# driver_board_v6_6tubes.net
KiCad netlist of a schematic drawn in EAGLE
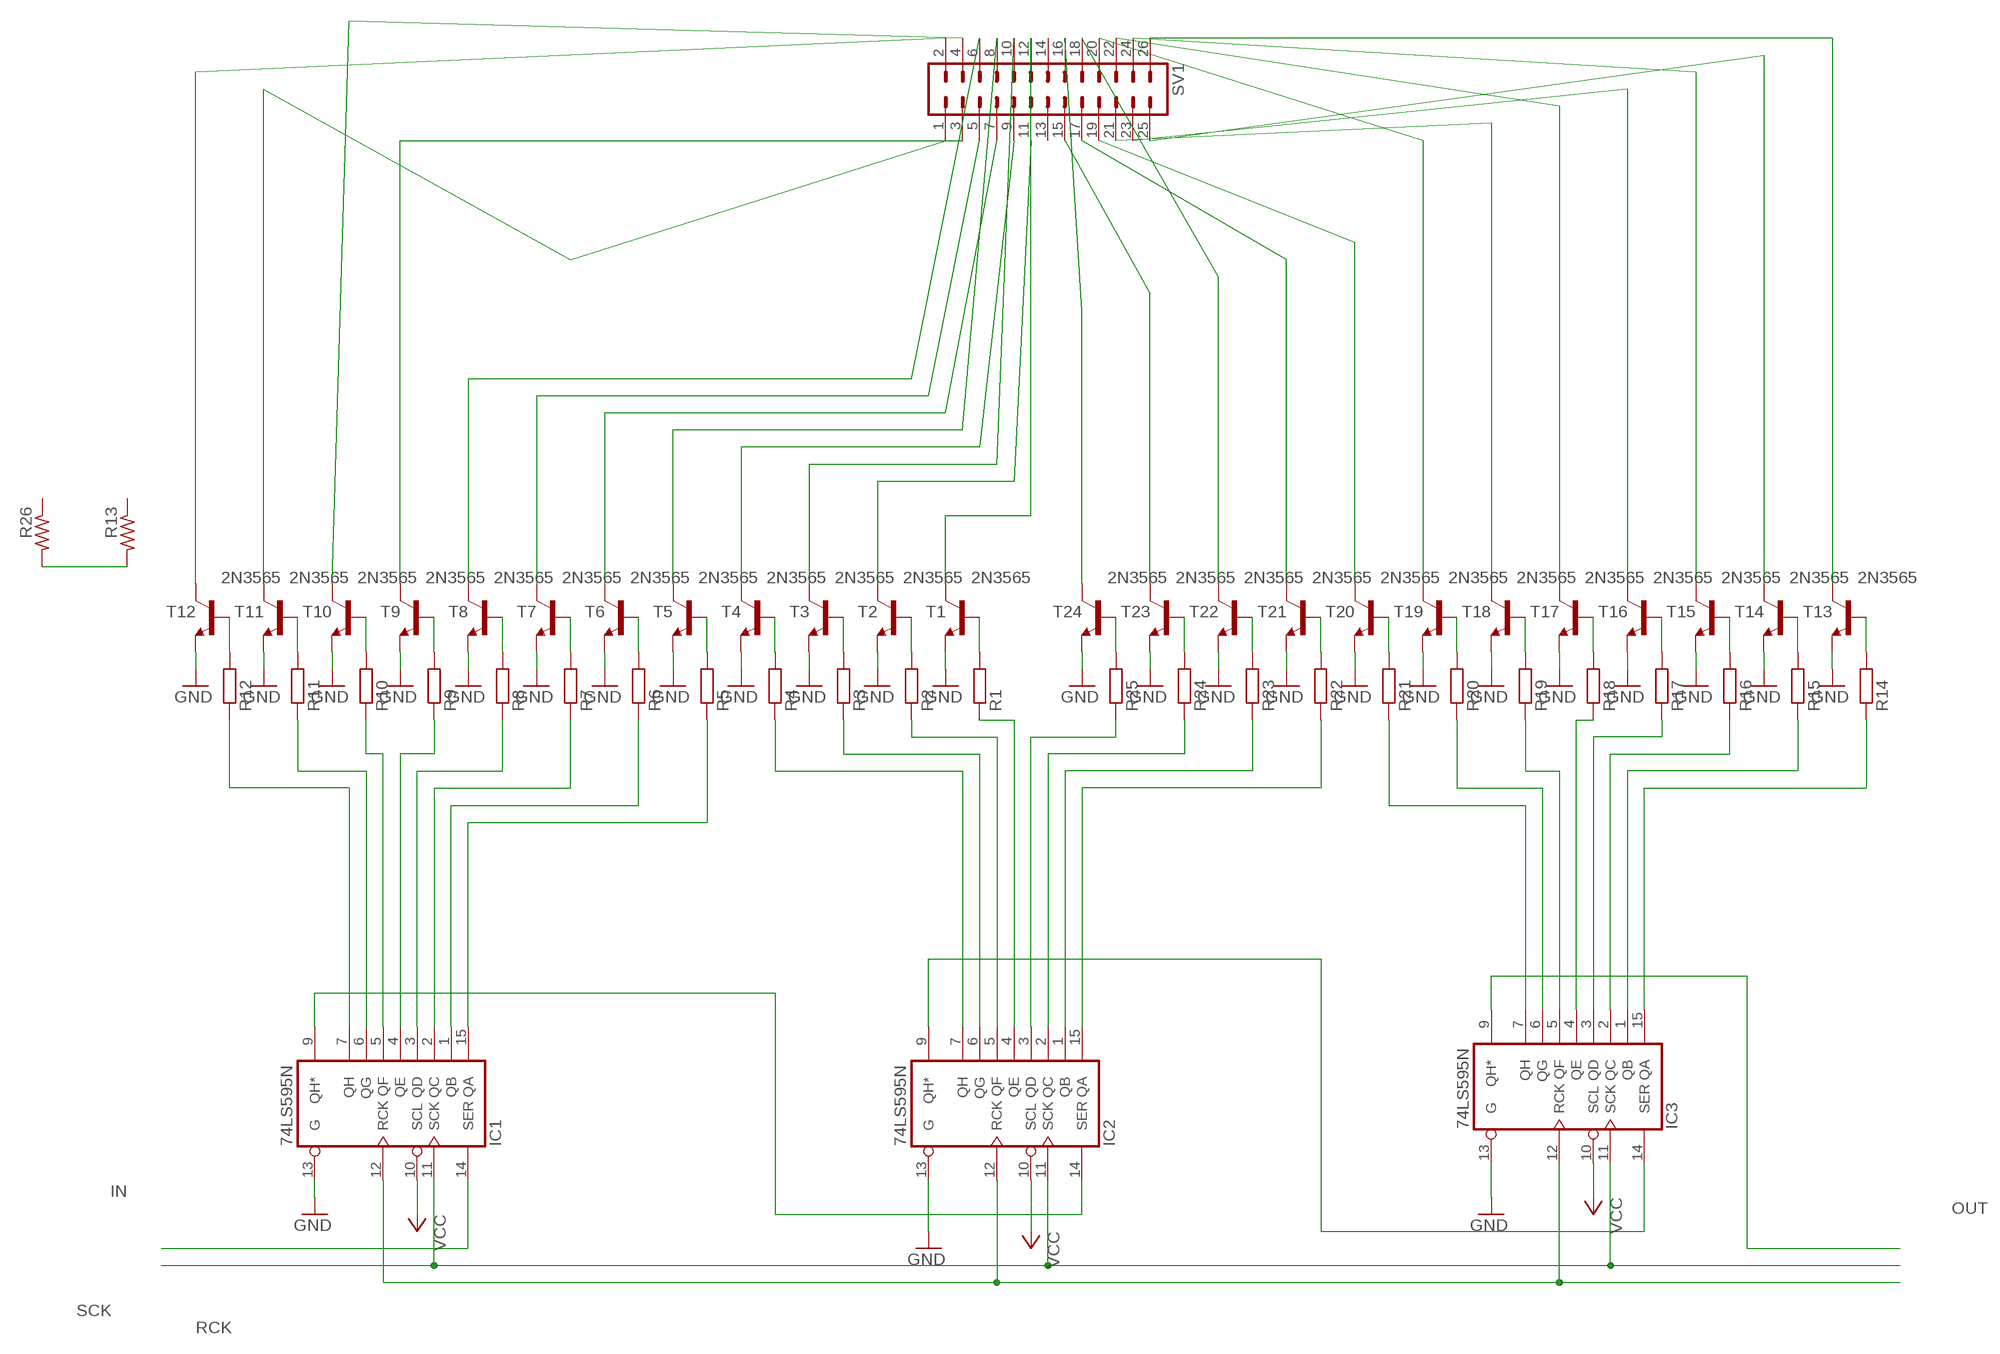
[diagram p0: schematic, sheet 1, part 1 of 2]
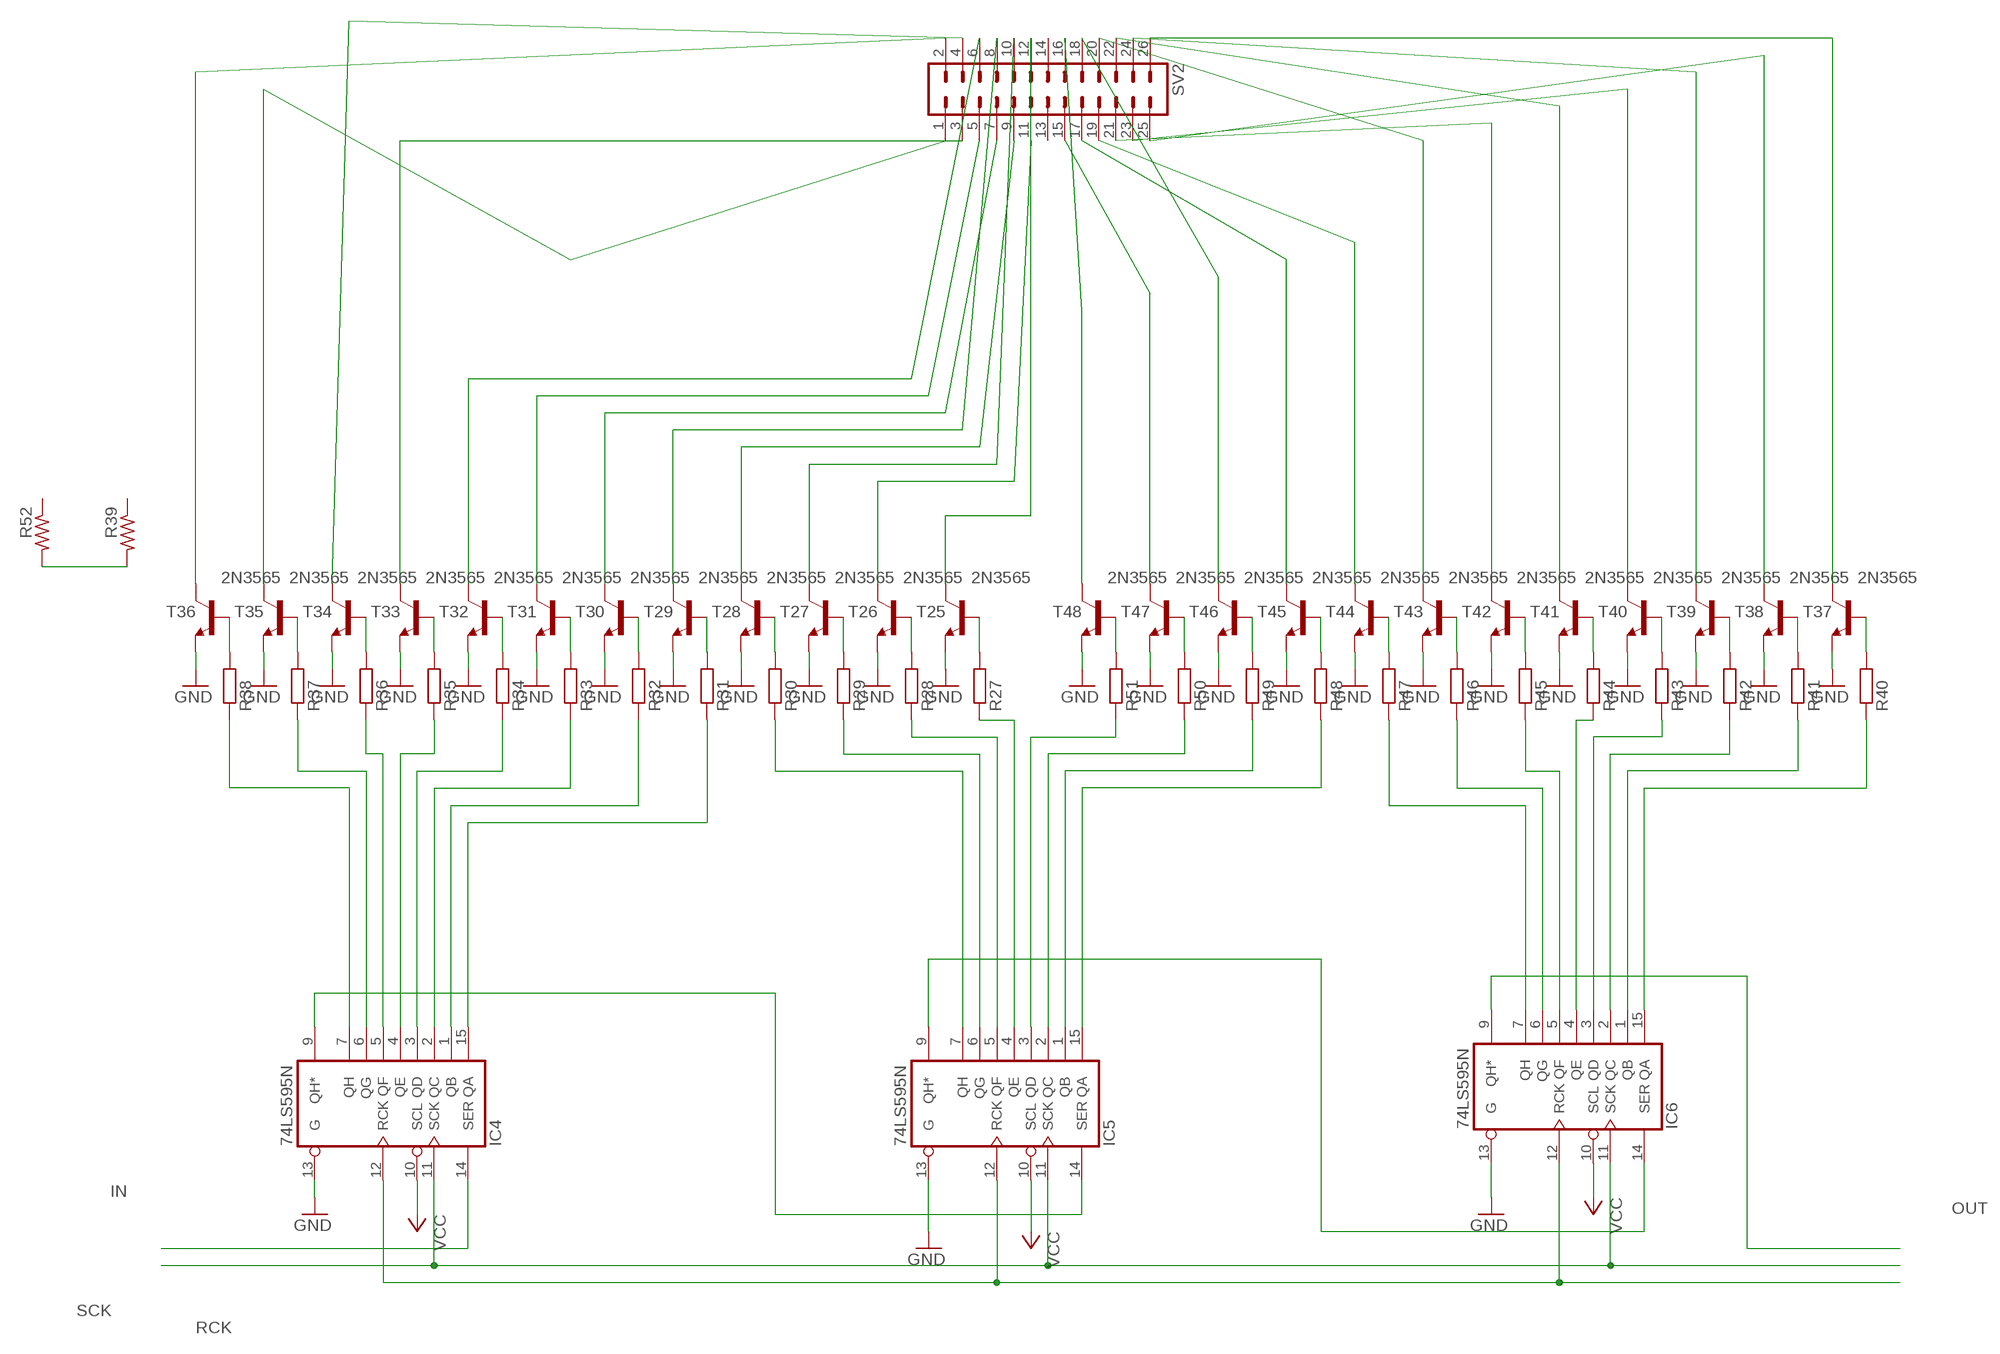
[diagram p1: schematic, sheet 1, part 2 of 2]

(export (version "E")
  (design (tool "Eeschema 10.0.6"))
  (components
    (comp (ref "IC1")
      (value "74LS595N")
      (footprint "eagle-import:DIL16")
      (libsource (lib "eagle-import") (part "74595NLS"))
    )
    (comp (ref "IC2")
      (value "74LS595N")
      (footprint "eagle-import:DIL16")
      (libsource (lib "eagle-import") (part "74595NLS"))
    )
    (comp (ref "IC3")
      (value "74LS595N")
      (footprint "eagle-import:DIL16")
      (libsource (lib "eagle-import") (part "74595NLS"))
    )
    (comp (ref "IC4")
      (value "74LS595N")
      (footprint "eagle-import:DIL16")
      (libsource (lib "eagle-import") (part "74595NLS"))
    )
    (comp (ref "IC5")
      (value "74LS595N")
      (footprint "eagle-import:DIL16")
      (libsource (lib "eagle-import") (part "74595NLS"))
    )
    (comp (ref "IC6")
      (value "74LS595N")
      (footprint "eagle-import:DIL16")
      (libsource (lib "eagle-import") (part "74595NLS"))
    )
    (comp (ref "R1")
      (value "R-EU_0207/2V")
      (footprint "eagle-import:0207_2V")
      (libsource (lib "eagle-import") (part "R-EU_0207/2V"))
    )
    (comp (ref "R2")
      (value "R-EU_0207/2V")
      (footprint "eagle-import:0207_2V")
      (libsource (lib "eagle-import") (part "R-EU_0207/2V"))
    )
    (comp (ref "R3")
      (value "R-EU_0207/2V")
      (footprint "eagle-import:0207_2V")
      (libsource (lib "eagle-import") (part "R-EU_0207/2V"))
    )
    (comp (ref "R4")
      (value "R-EU_0207/2V")
      (footprint "eagle-import:0207_2V")
      (libsource (lib "eagle-import") (part "R-EU_0207/2V"))
    )
    (comp (ref "R5")
      (value "R-EU_0207/2V")
      (footprint "eagle-import:0207_2V")
      (libsource (lib "eagle-import") (part "R-EU_0207/2V"))
    )
    (comp (ref "R6")
      (value "R-EU_0207/2V")
      (footprint "eagle-import:0207_2V")
      (libsource (lib "eagle-import") (part "R-EU_0207/2V"))
    )
    (comp (ref "R7")
      (value "R-EU_0207/2V")
      (footprint "eagle-import:0207_2V")
      (libsource (lib "eagle-import") (part "R-EU_0207/2V"))
    )
    (comp (ref "R8")
      (value "R-EU_0207/2V")
      (footprint "eagle-import:0207_2V")
      (libsource (lib "eagle-import") (part "R-EU_0207/2V"))
    )
    (comp (ref "R9")
      (value "R-EU_0207/2V")
      (footprint "eagle-import:0207_2V")
      (libsource (lib "eagle-import") (part "R-EU_0207/2V"))
    )
    (comp (ref "R10")
      (value "R-EU_0207/2V")
      (footprint "eagle-import:0207_2V")
      (libsource (lib "eagle-import") (part "R-EU_0207/2V"))
    )
    (comp (ref "R11")
      (value "R-EU_0207/2V")
      (footprint "eagle-import:0207_2V")
      (libsource (lib "eagle-import") (part "R-EU_0207/2V"))
    )
    (comp (ref "R12")
      (value "R-EU_0207/2V")
      (footprint "eagle-import:0207_2V")
      (libsource (lib "eagle-import") (part "R-EU_0207/2V"))
    )
    (comp (ref "R13")
      (value "R-US_0204/7")
      (footprint "eagle-import:0204_7")
      (libsource (lib "eagle-import") (part "R-US_0204/7"))
    )
    (comp (ref "R14")
      (value "R-EU_0207/2V")
      (footprint "eagle-import:0207_2V")
      (libsource (lib "eagle-import") (part "R-EU_0207/2V"))
    )
    (comp (ref "R15")
      (value "R-EU_0207/2V")
      (footprint "eagle-import:0207_2V")
      (libsource (lib "eagle-import") (part "R-EU_0207/2V"))
    )
    (comp (ref "R16")
      (value "R-EU_0207/2V")
      (footprint "eagle-import:0207_2V")
      (libsource (lib "eagle-import") (part "R-EU_0207/2V"))
    )
    (comp (ref "R17")
      (value "R-EU_0207/2V")
      (footprint "eagle-import:0207_2V")
      (libsource (lib "eagle-import") (part "R-EU_0207/2V"))
    )
    (comp (ref "R18")
      (value "R-EU_0207/2V")
      (footprint "eagle-import:0207_2V")
      (libsource (lib "eagle-import") (part "R-EU_0207/2V"))
    )
    (comp (ref "R19")
      (value "R-EU_0207/2V")
      (footprint "eagle-import:0207_2V")
      (libsource (lib "eagle-import") (part "R-EU_0207/2V"))
    )
    (comp (ref "R20")
      (value "R-EU_0207/2V")
      (footprint "eagle-import:0207_2V")
      (libsource (lib "eagle-import") (part "R-EU_0207/2V"))
    )
    (comp (ref "R21")
      (value "R-EU_0207/2V")
      (footprint "eagle-import:0207_2V")
      (libsource (lib "eagle-import") (part "R-EU_0207/2V"))
    )
    (comp (ref "R22")
      (value "R-EU_0207/2V")
      (footprint "eagle-import:0207_2V")
      (libsource (lib "eagle-import") (part "R-EU_0207/2V"))
    )
    (comp (ref "R23")
      (value "R-EU_0207/2V")
      (footprint "eagle-import:0207_2V")
      (libsource (lib "eagle-import") (part "R-EU_0207/2V"))
    )
    (comp (ref "R24")
      (value "R-EU_0207/2V")
      (footprint "eagle-import:0207_2V")
      (libsource (lib "eagle-import") (part "R-EU_0207/2V"))
    )
    (comp (ref "R25")
      (value "R-EU_0207/2V")
      (footprint "eagle-import:0207_2V")
      (libsource (lib "eagle-import") (part "R-EU_0207/2V"))
    )
    (comp (ref "R26")
      (value "R-US_0204/7")
      (footprint "eagle-import:0204_7")
      (libsource (lib "eagle-import") (part "R-US_0204/7"))
    )
    (comp (ref "R27")
      (value "R-EU_0207/2V")
      (footprint "eagle-import:0207_2V")
      (libsource (lib "eagle-import") (part "R-EU_0207/2V"))
    )
    (comp (ref "R28")
      (value "R-EU_0207/2V")
      (footprint "eagle-import:0207_2V")
      (libsource (lib "eagle-import") (part "R-EU_0207/2V"))
    )
    (comp (ref "R29")
      (value "R-EU_0207/2V")
      (footprint "eagle-import:0207_2V")
      (libsource (lib "eagle-import") (part "R-EU_0207/2V"))
    )
    (comp (ref "R30")
      (value "R-EU_0207/2V")
      (footprint "eagle-import:0207_2V")
      (libsource (lib "eagle-import") (part "R-EU_0207/2V"))
    )
    (comp (ref "R31")
      (value "R-EU_0207/2V")
      (footprint "eagle-import:0207_2V")
      (libsource (lib "eagle-import") (part "R-EU_0207/2V"))
    )
    (comp (ref "R32")
      (value "R-EU_0207/2V")
      (footprint "eagle-import:0207_2V")
      (libsource (lib "eagle-import") (part "R-EU_0207/2V"))
    )
    (comp (ref "R33")
      (value "R-EU_0207/2V")
      (footprint "eagle-import:0207_2V")
      (libsource (lib "eagle-import") (part "R-EU_0207/2V"))
    )
    (comp (ref "R34")
      (value "R-EU_0207/2V")
      (footprint "eagle-import:0207_2V")
      (libsource (lib "eagle-import") (part "R-EU_0207/2V"))
    )
    (comp (ref "R35")
      (value "R-EU_0207/2V")
      (footprint "eagle-import:0207_2V")
      (libsource (lib "eagle-import") (part "R-EU_0207/2V"))
    )
    (comp (ref "R36")
      (value "R-EU_0207/2V")
      (footprint "eagle-import:0207_2V")
      (libsource (lib "eagle-import") (part "R-EU_0207/2V"))
    )
    (comp (ref "R37")
      (value "R-EU_0207/2V")
      (footprint "eagle-import:0207_2V")
      (libsource (lib "eagle-import") (part "R-EU_0207/2V"))
    )
    (comp (ref "R38")
      (value "R-EU_0207/2V")
      (footprint "eagle-import:0207_2V")
      (libsource (lib "eagle-import") (part "R-EU_0207/2V"))
    )
    (comp (ref "R39")
      (value "R-US_0204/7")
      (footprint "eagle-import:0204_7")
      (libsource (lib "eagle-import") (part "R-US_0204/7"))
    )
    (comp (ref "R40")
      (value "R-EU_0207/2V")
      (footprint "eagle-import:0207_2V")
      (libsource (lib "eagle-import") (part "R-EU_0207/2V"))
    )
    (comp (ref "R41")
      (value "R-EU_0207/2V")
      (footprint "eagle-import:0207_2V")
      (libsource (lib "eagle-import") (part "R-EU_0207/2V"))
    )
    (comp (ref "R42")
      (value "R-EU_0207/2V")
      (footprint "eagle-import:0207_2V")
      (libsource (lib "eagle-import") (part "R-EU_0207/2V"))
    )
    (comp (ref "R43")
      (value "R-EU_0207/2V")
      (footprint "eagle-import:0207_2V")
      (libsource (lib "eagle-import") (part "R-EU_0207/2V"))
    )
    (comp (ref "R44")
      (value "R-EU_0207/2V")
      (footprint "eagle-import:0207_2V")
      (libsource (lib "eagle-import") (part "R-EU_0207/2V"))
    )
    (comp (ref "R45")
      (value "R-EU_0207/2V")
      (footprint "eagle-import:0207_2V")
      (libsource (lib "eagle-import") (part "R-EU_0207/2V"))
    )
    (comp (ref "R46")
      (value "R-EU_0207/2V")
      (footprint "eagle-import:0207_2V")
      (libsource (lib "eagle-import") (part "R-EU_0207/2V"))
    )
    (comp (ref "R47")
      (value "R-EU_0207/2V")
      (footprint "eagle-import:0207_2V")
      (libsource (lib "eagle-import") (part "R-EU_0207/2V"))
    )
    (comp (ref "R48")
      (value "R-EU_0207/2V")
      (footprint "eagle-import:0207_2V")
      (libsource (lib "eagle-import") (part "R-EU_0207/2V"))
    )
    (comp (ref "R49")
      (value "R-EU_0207/2V")
      (footprint "eagle-import:0207_2V")
      (libsource (lib "eagle-import") (part "R-EU_0207/2V"))
    )
    (comp (ref "R50")
      (value "R-EU_0207/2V")
      (footprint "eagle-import:0207_2V")
      (libsource (lib "eagle-import") (part "R-EU_0207/2V"))
    )
    (comp (ref "R51")
      (value "R-EU_0207/2V")
      (footprint "eagle-import:0207_2V")
      (libsource (lib "eagle-import") (part "R-EU_0207/2V"))
    )
    (comp (ref "R52")
      (value "R-US_0204/7")
      (footprint "eagle-import:0204_7")
      (libsource (lib "eagle-import") (part "R-US_0204/7"))
    )
    (comp (ref "SV1")
      (value "MA13-2")
      (footprint "eagle-import:MA13-2")
      (libsource (lib "eagle-import") (part "MA13-2"))
    )
    (comp (ref "SV2")
      (value "MA13-2")
      (footprint "eagle-import:MA13-2")
      (libsource (lib "eagle-import") (part "MA13-2"))
    )
    (comp (ref "T1")
      (value "2N3565")
      (footprint "eagle-import:TO92")
      (libsource (lib "eagle-import") (part "2N3565"))
    )
    (comp (ref "T2")
      (value "2N3565")
      (footprint "eagle-import:TO92")
      (libsource (lib "eagle-import") (part "2N3565"))
    )
    (comp (ref "T3")
      (value "2N3565")
      (footprint "eagle-import:TO92")
      (libsource (lib "eagle-import") (part "2N3565"))
    )
    (comp (ref "T4")
      (value "2N3565")
      (footprint "eagle-import:TO92")
      (libsource (lib "eagle-import") (part "2N3565"))
    )
    (comp (ref "T5")
      (value "2N3565")
      (footprint "eagle-import:TO92")
      (libsource (lib "eagle-import") (part "2N3565"))
    )
    (comp (ref "T6")
      (value "2N3565")
      (footprint "eagle-import:TO92")
      (libsource (lib "eagle-import") (part "2N3565"))
    )
    (comp (ref "T7")
      (value "2N3565")
      (footprint "eagle-import:TO92")
      (libsource (lib "eagle-import") (part "2N3565"))
    )
    (comp (ref "T8")
      (value "2N3565")
      (footprint "eagle-import:TO92")
      (libsource (lib "eagle-import") (part "2N3565"))
    )
    (comp (ref "T9")
      (value "2N3565")
      (footprint "eagle-import:TO92")
      (libsource (lib "eagle-import") (part "2N3565"))
    )
    (comp (ref "T10")
      (value "2N3565")
      (footprint "eagle-import:TO92")
      (libsource (lib "eagle-import") (part "2N3565"))
    )
    (comp (ref "T11")
      (value "2N3565")
      (footprint "eagle-import:TO92")
      (libsource (lib "eagle-import") (part "2N3565"))
    )
    (comp (ref "T12")
      (value "2N3565")
      (footprint "eagle-import:TO92")
      (libsource (lib "eagle-import") (part "2N3565"))
    )
    (comp (ref "T13")
      (value "2N3565")
      (footprint "eagle-import:TO92")
      (libsource (lib "eagle-import") (part "2N3565"))
    )
    (comp (ref "T14")
      (value "2N3565")
      (footprint "eagle-import:TO92")
      (libsource (lib "eagle-import") (part "2N3565"))
    )
    (comp (ref "T15")
      (value "2N3565")
      (footprint "eagle-import:TO92")
      (libsource (lib "eagle-import") (part "2N3565"))
    )
    (comp (ref "T16")
      (value "2N3565")
      (footprint "eagle-import:TO92")
      (libsource (lib "eagle-import") (part "2N3565"))
    )
    (comp (ref "T17")
      (value "2N3565")
      (footprint "eagle-import:TO92")
      (libsource (lib "eagle-import") (part "2N3565"))
    )
    (comp (ref "T18")
      (value "2N3565")
      (footprint "eagle-import:TO92")
      (libsource (lib "eagle-import") (part "2N3565"))
    )
    (comp (ref "T19")
      (value "2N3565")
      (footprint "eagle-import:TO92")
      (libsource (lib "eagle-import") (part "2N3565"))
    )
    (comp (ref "T20")
      (value "2N3565")
      (footprint "eagle-import:TO92")
      (libsource (lib "eagle-import") (part "2N3565"))
    )
    (comp (ref "T21")
      (value "2N3565")
      (footprint "eagle-import:TO92")
      (libsource (lib "eagle-import") (part "2N3565"))
    )
    (comp (ref "T22")
      (value "2N3565")
      (footprint "eagle-import:TO92")
      (libsource (lib "eagle-import") (part "2N3565"))
    )
    (comp (ref "T23")
      (value "2N3565")
      (footprint "eagle-import:TO92")
      (libsource (lib "eagle-import") (part "2N3565"))
    )
    (comp (ref "T24")
      (value "2N3565")
      (footprint "eagle-import:TO92")
      (libsource (lib "eagle-import") (part "2N3565"))
    )
    (comp (ref "T25")
      (value "2N3565")
      (footprint "eagle-import:TO92")
      (libsource (lib "eagle-import") (part "2N3565"))
    )
    (comp (ref "T26")
      (value "2N3565")
      (footprint "eagle-import:TO92")
      (libsource (lib "eagle-import") (part "2N3565"))
    )
    (comp (ref "T27")
      (value "2N3565")
      (footprint "eagle-import:TO92")
      (libsource (lib "eagle-import") (part "2N3565"))
    )
    (comp (ref "T28")
      (value "2N3565")
      (footprint "eagle-import:TO92")
      (libsource (lib "eagle-import") (part "2N3565"))
    )
    (comp (ref "T29")
      (value "2N3565")
      (footprint "eagle-import:TO92")
      (libsource (lib "eagle-import") (part "2N3565"))
    )
    (comp (ref "T30")
      (value "2N3565")
      (footprint "eagle-import:TO92")
      (libsource (lib "eagle-import") (part "2N3565"))
    )
    (comp (ref "T31")
      (value "2N3565")
      (footprint "eagle-import:TO92")
      (libsource (lib "eagle-import") (part "2N3565"))
    )
    (comp (ref "T32")
      (value "2N3565")
      (footprint "eagle-import:TO92")
      (libsource (lib "eagle-import") (part "2N3565"))
    )
    (comp (ref "T33")
      (value "2N3565")
      (footprint "eagle-import:TO92")
      (libsource (lib "eagle-import") (part "2N3565"))
    )
    (comp (ref "T34")
      (value "2N3565")
      (footprint "eagle-import:TO92")
      (libsource (lib "eagle-import") (part "2N3565"))
    )
    (comp (ref "T35")
      (value "2N3565")
      (footprint "eagle-import:TO92")
      (libsource (lib "eagle-import") (part "2N3565"))
    )
    (comp (ref "T36")
      (value "2N3565")
      (footprint "eagle-import:TO92")
      (libsource (lib "eagle-import") (part "2N3565"))
    )
    (comp (ref "T37")
      (value "2N3565")
      (footprint "eagle-import:TO92")
      (libsource (lib "eagle-import") (part "2N3565"))
    )
    (comp (ref "T38")
      (value "2N3565")
      (footprint "eagle-import:TO92")
      (libsource (lib "eagle-import") (part "2N3565"))
    )
    (comp (ref "T39")
      (value "2N3565")
      (footprint "eagle-import:TO92")
      (libsource (lib "eagle-import") (part "2N3565"))
    )
    (comp (ref "T40")
      (value "2N3565")
      (footprint "eagle-import:TO92")
      (libsource (lib "eagle-import") (part "2N3565"))
    )
    (comp (ref "T41")
      (value "2N3565")
      (footprint "eagle-import:TO92")
      (libsource (lib "eagle-import") (part "2N3565"))
    )
    (comp (ref "T42")
      (value "2N3565")
      (footprint "eagle-import:TO92")
      (libsource (lib "eagle-import") (part "2N3565"))
    )
    (comp (ref "T43")
      (value "2N3565")
      (footprint "eagle-import:TO92")
      (libsource (lib "eagle-import") (part "2N3565"))
    )
    (comp (ref "T44")
      (value "2N3565")
      (footprint "eagle-import:TO92")
      (libsource (lib "eagle-import") (part "2N3565"))
    )
    (comp (ref "T45")
      (value "2N3565")
      (footprint "eagle-import:TO92")
      (libsource (lib "eagle-import") (part "2N3565"))
    )
    (comp (ref "T46")
      (value "2N3565")
      (footprint "eagle-import:TO92")
      (libsource (lib "eagle-import") (part "2N3565"))
    )
    (comp (ref "T47")
      (value "2N3565")
      (footprint "eagle-import:TO92")
      (libsource (lib "eagle-import") (part "2N3565"))
    )
    (comp (ref "T48")
      (value "2N3565")
      (footprint "eagle-import:TO92")
      (libsource (lib "eagle-import") (part "2N3565"))
    )
  )
  (nets
    (net (code "1") (name "/IN") (class "Default")
      (node (ref "IC1") (pin "14") (pinfunction "SER_14") (pintype "input"))
      (node (ref "IC4") (pin "14") (pinfunction "SER_14") (pintype "input"))
    )
    (net (code "2") (name "/OUT") (class "Default")
      (node (ref "IC3") (pin "9") (pinfunction "QH*_9") (pintype "tri_state"))
      (node (ref "IC6") (pin "9") (pinfunction "QH*_9") (pintype "tri_state"))
    )
    (net (code "3") (name "/RCK") (class "Default")
      (node (ref "IC1") (pin "12") (pinfunction "RCK_12") (pintype "input"))
      (node (ref "IC2") (pin "12") (pinfunction "RCK_12") (pintype "input"))
      (node (ref "IC3") (pin "12") (pinfunction "RCK_12") (pintype "input"))
      (node (ref "IC4") (pin "12") (pinfunction "RCK_12") (pintype "input"))
      (node (ref "IC5") (pin "12") (pinfunction "RCK_12") (pintype "input"))
      (node (ref "IC6") (pin "12") (pinfunction "RCK_12") (pintype "input"))
    )
    (net (code "4") (name "/SCK") (class "Default")
      (node (ref "IC1") (pin "11") (pinfunction "SCK_11") (pintype "input"))
      (node (ref "IC2") (pin "11") (pinfunction "SCK_11") (pintype "input"))
      (node (ref "IC3") (pin "11") (pinfunction "SCK_11") (pintype "input"))
      (node (ref "IC4") (pin "11") (pinfunction "SCK_11") (pintype "input"))
      (node (ref "IC5") (pin "11") (pinfunction "SCK_11") (pintype "input"))
      (node (ref "IC6") (pin "11") (pinfunction "SCK_11") (pintype "input"))
    )
    (net (code "5") (name "GND") (class "Default")
      (node (ref "IC1") (pin "13") (pinfunction "G_13") (pintype "input"))
      (node (ref "IC2") (pin "13") (pinfunction "G_13") (pintype "input"))
      (node (ref "IC3") (pin "13") (pinfunction "G_13") (pintype "input"))
      (node (ref "IC4") (pin "13") (pinfunction "G_13") (pintype "input"))
      (node (ref "IC5") (pin "13") (pinfunction "G_13") (pintype "input"))
      (node (ref "IC6") (pin "13") (pinfunction "G_13") (pintype "input"))
      (node (ref "T1") (pin "3") (pinfunction "E_3") (pintype "passive"))
      (node (ref "T10") (pin "3") (pinfunction "E_3") (pintype "passive"))
      (node (ref "T11") (pin "3") (pinfunction "E_3") (pintype "passive"))
      (node (ref "T12") (pin "3") (pinfunction "E_3") (pintype "passive"))
      (node (ref "T13") (pin "3") (pinfunction "E_3") (pintype "passive"))
      (node (ref "T14") (pin "3") (pinfunction "E_3") (pintype "passive"))
      (node (ref "T15") (pin "3") (pinfunction "E_3") (pintype "passive"))
      (node (ref "T16") (pin "3") (pinfunction "E_3") (pintype "passive"))
      (node (ref "T17") (pin "3") (pinfunction "E_3") (pintype "passive"))
      (node (ref "T18") (pin "3") (pinfunction "E_3") (pintype "passive"))
      (node (ref "T19") (pin "3") (pinfunction "E_3") (pintype "passive"))
      (node (ref "T2") (pin "3") (pinfunction "E_3") (pintype "passive"))
      (node (ref "T20") (pin "3") (pinfunction "E_3") (pintype "passive"))
      (node (ref "T21") (pin "3") (pinfunction "E_3") (pintype "passive"))
      (node (ref "T22") (pin "3") (pinfunction "E_3") (pintype "passive"))
      (node (ref "T23") (pin "3") (pinfunction "E_3") (pintype "passive"))
      (node (ref "T24") (pin "3") (pinfunction "E_3") (pintype "passive"))
      (node (ref "T25") (pin "3") (pinfunction "E_3") (pintype "passive"))
      (node (ref "T26") (pin "3") (pinfunction "E_3") (pintype "passive"))
      (node (ref "T27") (pin "3") (pinfunction "E_3") (pintype "passive"))
      (node (ref "T28") (pin "3") (pinfunction "E_3") (pintype "passive"))
      (node (ref "T29") (pin "3") (pinfunction "E_3") (pintype "passive"))
      (node (ref "T3") (pin "3") (pinfunction "E_3") (pintype "passive"))
      (node (ref "T30") (pin "3") (pinfunction "E_3") (pintype "passive"))
      (node (ref "T31") (pin "3") (pinfunction "E_3") (pintype "passive"))
      (node (ref "T32") (pin "3") (pinfunction "E_3") (pintype "passive"))
      (node (ref "T33") (pin "3") (pinfunction "E_3") (pintype "passive"))
      (node (ref "T34") (pin "3") (pinfunction "E_3") (pintype "passive"))
      (node (ref "T35") (pin "3") (pinfunction "E_3") (pintype "passive"))
      (node (ref "T36") (pin "3") (pinfunction "E_3") (pintype "passive"))
      (node (ref "T37") (pin "3") (pinfunction "E_3") (pintype "passive"))
      (node (ref "T38") (pin "3") (pinfunction "E_3") (pintype "passive"))
      (node (ref "T39") (pin "3") (pinfunction "E_3") (pintype "passive"))
      (node (ref "T4") (pin "3") (pinfunction "E_3") (pintype "passive"))
      (node (ref "T40") (pin "3") (pinfunction "E_3") (pintype "passive"))
      (node (ref "T41") (pin "3") (pinfunction "E_3") (pintype "passive"))
      (node (ref "T42") (pin "3") (pinfunction "E_3") (pintype "passive"))
      (node (ref "T43") (pin "3") (pinfunction "E_3") (pintype "passive"))
      (node (ref "T44") (pin "3") (pinfunction "E_3") (pintype "passive"))
      (node (ref "T45") (pin "3") (pinfunction "E_3") (pintype "passive"))
      (node (ref "T46") (pin "3") (pinfunction "E_3") (pintype "passive"))
      (node (ref "T47") (pin "3") (pinfunction "E_3") (pintype "passive"))
      (node (ref "T48") (pin "3") (pinfunction "E_3") (pintype "passive"))
      (node (ref "T5") (pin "3") (pinfunction "E_3") (pintype "passive"))
      (node (ref "T6") (pin "3") (pinfunction "E_3") (pintype "passive"))
      (node (ref "T7") (pin "3") (pinfunction "E_3") (pintype "passive"))
      (node (ref "T8") (pin "3") (pinfunction "E_3") (pintype "passive"))
      (node (ref "T9") (pin "3") (pinfunction "E_3") (pintype "passive"))
    )
    (net (code "6") (name "Net-(IC1A-QA)") (class "Default")
      (node (ref "IC1") (pin "15") (pinfunction "QA_15") (pintype "tri_state"))
      (node (ref "R5") (pin "1") (pinfunction "1_1") (pintype "passive"))
    )
    (net (code "7") (name "Net-(IC1A-QB)") (class "Default")
      (node (ref "IC1") (pin "1") (pinfunction "QB_1") (pintype "tri_state"))
      (node (ref "R6") (pin "1") (pinfunction "1_1") (pintype "passive"))
    )
    (net (code "8") (name "Net-(IC1A-QC)") (class "Default")
      (node (ref "IC1") (pin "2") (pinfunction "QC_2") (pintype "tri_state"))
      (node (ref "R7") (pin "1") (pinfunction "1_1") (pintype "passive"))
    )
    (net (code "9") (name "Net-(IC1A-QD)") (class "Default")
      (node (ref "IC1") (pin "3") (pinfunction "QD_3") (pintype "tri_state"))
      (node (ref "R8") (pin "1") (pinfunction "1_1") (pintype "passive"))
    )
    (net (code "10") (name "Net-(IC1A-QE)") (class "Default")
      (node (ref "IC1") (pin "4") (pinfunction "QE_4") (pintype "tri_state"))
      (node (ref "R9") (pin "1") (pinfunction "1_1") (pintype "passive"))
    )
    (net (code "11") (name "Net-(IC1A-QF)") (class "Default")
      (node (ref "IC1") (pin "5") (pinfunction "QF_5") (pintype "tri_state"))
      (node (ref "R10") (pin "1") (pinfunction "1_1") (pintype "passive"))
    )
    (net (code "12") (name "Net-(IC1A-QG)") (class "Default")
      (node (ref "IC1") (pin "6") (pinfunction "QG_6") (pintype "tri_state"))
      (node (ref "R11") (pin "1") (pinfunction "1_1") (pintype "passive"))
    )
    (net (code "13") (name "Net-(IC1A-QH)") (class "Default")
      (node (ref "IC1") (pin "7") (pinfunction "QH_7") (pintype "tri_state"))
      (node (ref "R12") (pin "1") (pinfunction "1_1") (pintype "passive"))
    )
    (net (code "14") (name "Net-(IC1A-QH*)") (class "Default")
      (node (ref "IC1") (pin "9") (pinfunction "QH*_9") (pintype "tri_state"))
      (node (ref "IC2") (pin "14") (pinfunction "SER_14") (pintype "input"))
    )
    (net (code "15") (name "Net-(IC2A-QA)") (class "Default")
      (node (ref "IC2") (pin "15") (pinfunction "QA_15") (pintype "tri_state"))
      (node (ref "R22") (pin "1") (pinfunction "1_1") (pintype "passive"))
    )
    (net (code "16") (name "Net-(IC2A-QB)") (class "Default")
      (node (ref "IC2") (pin "1") (pinfunction "QB_1") (pintype "tri_state"))
      (node (ref "R23") (pin "1") (pinfunction "1_1") (pintype "passive"))
    )
    (net (code "17") (name "Net-(IC2A-QC)") (class "Default")
      (node (ref "IC2") (pin "2") (pinfunction "QC_2") (pintype "tri_state"))
      (node (ref "R24") (pin "1") (pinfunction "1_1") (pintype "passive"))
    )
    (net (code "18") (name "Net-(IC2A-QD)") (class "Default")
      (node (ref "IC2") (pin "3") (pinfunction "QD_3") (pintype "tri_state"))
      (node (ref "R25") (pin "1") (pinfunction "1_1") (pintype "passive"))
    )
    (net (code "19") (name "Net-(IC2A-QE)") (class "Default")
      (node (ref "IC2") (pin "4") (pinfunction "QE_4") (pintype "tri_state"))
      (node (ref "R1") (pin "1") (pinfunction "1_1") (pintype "passive"))
    )
    (net (code "20") (name "Net-(IC2A-QF)") (class "Default")
      (node (ref "IC2") (pin "5") (pinfunction "QF_5") (pintype "tri_state"))
      (node (ref "R2") (pin "1") (pinfunction "1_1") (pintype "passive"))
    )
    (net (code "21") (name "Net-(IC2A-QG)") (class "Default")
      (node (ref "IC2") (pin "6") (pinfunction "QG_6") (pintype "tri_state"))
      (node (ref "R3") (pin "1") (pinfunction "1_1") (pintype "passive"))
    )
    (net (code "22") (name "Net-(IC2A-QH)") (class "Default")
      (node (ref "IC2") (pin "7") (pinfunction "QH_7") (pintype "tri_state"))
      (node (ref "R4") (pin "1") (pinfunction "1_1") (pintype "passive"))
    )
    (net (code "23") (name "Net-(IC2A-QH*)") (class "Default")
      (node (ref "IC2") (pin "9") (pinfunction "QH*_9") (pintype "tri_state"))
      (node (ref "IC3") (pin "14") (pinfunction "SER_14") (pintype "input"))
    )
    (net (code "24") (name "Net-(IC3A-QA)") (class "Default")
      (node (ref "IC3") (pin "15") (pinfunction "QA_15") (pintype "tri_state"))
      (node (ref "R14") (pin "1") (pinfunction "1_1") (pintype "passive"))
    )
    (net (code "25") (name "Net-(IC3A-QB)") (class "Default")
      (node (ref "IC3") (pin "1") (pinfunction "QB_1") (pintype "tri_state"))
      (node (ref "R15") (pin "1") (pinfunction "1_1") (pintype "passive"))
    )
    (net (code "26") (name "Net-(IC3A-QC)") (class "Default")
      (node (ref "IC3") (pin "2") (pinfunction "QC_2") (pintype "tri_state"))
      (node (ref "R16") (pin "1") (pinfunction "1_1") (pintype "passive"))
    )
    (net (code "27") (name "Net-(IC3A-QD)") (class "Default")
      (node (ref "IC3") (pin "3") (pinfunction "QD_3") (pintype "tri_state"))
      (node (ref "R17") (pin "1") (pinfunction "1_1") (pintype "passive"))
    )
    (net (code "28") (name "Net-(IC3A-QE)") (class "Default")
      (node (ref "IC3") (pin "4") (pinfunction "QE_4") (pintype "tri_state"))
      (node (ref "R18") (pin "1") (pinfunction "1_1") (pintype "passive"))
    )
    (net (code "29") (name "Net-(IC3A-QF)") (class "Default")
      (node (ref "IC3") (pin "5") (pinfunction "QF_5") (pintype "tri_state"))
      (node (ref "R19") (pin "1") (pinfunction "1_1") (pintype "passive"))
    )
    (net (code "30") (name "Net-(IC3A-QG)") (class "Default")
      (node (ref "IC3") (pin "6") (pinfunction "QG_6") (pintype "tri_state"))
      (node (ref "R20") (pin "1") (pinfunction "1_1") (pintype "passive"))
    )
    (net (code "31") (name "Net-(IC3A-QH)") (class "Default")
      (node (ref "IC3") (pin "7") (pinfunction "QH_7") (pintype "tri_state"))
      (node (ref "R21") (pin "1") (pinfunction "1_1") (pintype "passive"))
    )
    (net (code "32") (name "Net-(IC4A-QA)") (class "Default")
      (node (ref "IC4") (pin "15") (pinfunction "QA_15") (pintype "tri_state"))
      (node (ref "R31") (pin "1") (pinfunction "1_1") (pintype "passive"))
    )
    (net (code "33") (name "Net-(IC4A-QB)") (class "Default")
      (node (ref "IC4") (pin "1") (pinfunction "QB_1") (pintype "tri_state"))
      (node (ref "R32") (pin "1") (pinfunction "1_1") (pintype "passive"))
    )
    (net (code "34") (name "Net-(IC4A-QC)") (class "Default")
      (node (ref "IC4") (pin "2") (pinfunction "QC_2") (pintype "tri_state"))
      (node (ref "R33") (pin "1") (pinfunction "1_1") (pintype "passive"))
    )
    (net (code "35") (name "Net-(IC4A-QD)") (class "Default")
      (node (ref "IC4") (pin "3") (pinfunction "QD_3") (pintype "tri_state"))
      (node (ref "R34") (pin "1") (pinfunction "1_1") (pintype "passive"))
    )
    (net (code "36") (name "Net-(IC4A-QE)") (class "Default")
      (node (ref "IC4") (pin "4") (pinfunction "QE_4") (pintype "tri_state"))
      (node (ref "R35") (pin "1") (pinfunction "1_1") (pintype "passive"))
    )
    (net (code "37") (name "Net-(IC4A-QF)") (class "Default")
      (node (ref "IC4") (pin "5") (pinfunction "QF_5") (pintype "tri_state"))
      (node (ref "R36") (pin "1") (pinfunction "1_1") (pintype "passive"))
    )
    (net (code "38") (name "Net-(IC4A-QG)") (class "Default")
      (node (ref "IC4") (pin "6") (pinfunction "QG_6") (pintype "tri_state"))
      (node (ref "R37") (pin "1") (pinfunction "1_1") (pintype "passive"))
    )
    (net (code "39") (name "Net-(IC4A-QH)") (class "Default")
      (node (ref "IC4") (pin "7") (pinfunction "QH_7") (pintype "tri_state"))
      (node (ref "R38") (pin "1") (pinfunction "1_1") (pintype "passive"))
    )
    (net (code "40") (name "Net-(IC4A-QH*)") (class "Default")
      (node (ref "IC4") (pin "9") (pinfunction "QH*_9") (pintype "tri_state"))
      (node (ref "IC5") (pin "14") (pinfunction "SER_14") (pintype "input"))
    )
    (net (code "41") (name "Net-(IC5A-QA)") (class "Default")
      (node (ref "IC5") (pin "15") (pinfunction "QA_15") (pintype "tri_state"))
      (node (ref "R48") (pin "1") (pinfunction "1_1") (pintype "passive"))
    )
    (net (code "42") (name "Net-(IC5A-QB)") (class "Default")
      (node (ref "IC5") (pin "1") (pinfunction "QB_1") (pintype "tri_state"))
      (node (ref "R49") (pin "1") (pinfunction "1_1") (pintype "passive"))
    )
    (net (code "43") (name "Net-(IC5A-QC)") (class "Default")
      (node (ref "IC5") (pin "2") (pinfunction "QC_2") (pintype "tri_state"))
      (node (ref "R50") (pin "1") (pinfunction "1_1") (pintype "passive"))
    )
    (net (code "44") (name "Net-(IC5A-QD)") (class "Default")
      (node (ref "IC5") (pin "3") (pinfunction "QD_3") (pintype "tri_state"))
      (node (ref "R51") (pin "1") (pinfunction "1_1") (pintype "passive"))
    )
    (net (code "45") (name "Net-(IC5A-QE)") (class "Default")
      (node (ref "IC5") (pin "4") (pinfunction "QE_4") (pintype "tri_state"))
      (node (ref "R27") (pin "1") (pinfunction "1_1") (pintype "passive"))
    )
    (net (code "46") (name "Net-(IC5A-QF)") (class "Default")
      (node (ref "IC5") (pin "5") (pinfunction "QF_5") (pintype "tri_state"))
      (node (ref "R28") (pin "1") (pinfunction "1_1") (pintype "passive"))
    )
    (net (code "47") (name "Net-(IC5A-QG)") (class "Default")
      (node (ref "IC5") (pin "6") (pinfunction "QG_6") (pintype "tri_state"))
      (node (ref "R29") (pin "1") (pinfunction "1_1") (pintype "passive"))
    )
    (net (code "48") (name "Net-(IC5A-QH)") (class "Default")
      (node (ref "IC5") (pin "7") (pinfunction "QH_7") (pintype "tri_state"))
      (node (ref "R30") (pin "1") (pinfunction "1_1") (pintype "passive"))
    )
    (net (code "49") (name "Net-(IC5A-QH*)") (class "Default")
      (node (ref "IC5") (pin "9") (pinfunction "QH*_9") (pintype "tri_state"))
      (node (ref "IC6") (pin "14") (pinfunction "SER_14") (pintype "input"))
    )
    (net (code "50") (name "Net-(IC6A-QA)") (class "Default")
      (node (ref "IC6") (pin "15") (pinfunction "QA_15") (pintype "tri_state"))
      (node (ref "R40") (pin "1") (pinfunction "1_1") (pintype "passive"))
    )
    (net (code "51") (name "Net-(IC6A-QB)") (class "Default")
      (node (ref "IC6") (pin "1") (pinfunction "QB_1") (pintype "tri_state"))
      (node (ref "R41") (pin "1") (pinfunction "1_1") (pintype "passive"))
    )
    (net (code "52") (name "Net-(IC6A-QC)") (class "Default")
      (node (ref "IC6") (pin "2") (pinfunction "QC_2") (pintype "tri_state"))
      (node (ref "R42") (pin "1") (pinfunction "1_1") (pintype "passive"))
    )
    (net (code "53") (name "Net-(IC6A-QD)") (class "Default")
      (node (ref "IC6") (pin "3") (pinfunction "QD_3") (pintype "tri_state"))
      (node (ref "R43") (pin "1") (pinfunction "1_1") (pintype "passive"))
    )
    (net (code "54") (name "Net-(IC6A-QE)") (class "Default")
      (node (ref "IC6") (pin "4") (pinfunction "QE_4") (pintype "tri_state"))
      (node (ref "R44") (pin "1") (pinfunction "1_1") (pintype "passive"))
    )
    (net (code "55") (name "Net-(IC6A-QF)") (class "Default")
      (node (ref "IC6") (pin "5") (pinfunction "QF_5") (pintype "tri_state"))
      (node (ref "R45") (pin "1") (pinfunction "1_1") (pintype "passive"))
    )
    (net (code "56") (name "Net-(IC6A-QG)") (class "Default")
      (node (ref "IC6") (pin "6") (pinfunction "QG_6") (pintype "tri_state"))
      (node (ref "R46") (pin "1") (pinfunction "1_1") (pintype "passive"))
    )
    (net (code "57") (name "Net-(IC6A-QH)") (class "Default")
      (node (ref "IC6") (pin "7") (pinfunction "QH_7") (pintype "tri_state"))
      (node (ref "R47") (pin "1") (pinfunction "1_1") (pintype "passive"))
    )
    (net (code "58") (name "Net-(R13-Pad2)") (class "Default")
      (node (ref "R13") (pin "2") (pinfunction "2_2") (pintype "passive"))
      (node (ref "R26") (pin "2") (pinfunction "2_2") (pintype "passive"))
    )
    (net (code "59") (name "Net-(R39-Pad2)") (class "Default")
      (node (ref "R39") (pin "2") (pinfunction "2_2") (pintype "passive"))
      (node (ref "R52") (pin "2") (pinfunction "2_2") (pintype "passive"))
    )
    (net (code "60") (name "Net-(T1-B)") (class "Default")
      (node (ref "R1") (pin "2") (pinfunction "2_2") (pintype "passive"))
      (node (ref "T1") (pin "2") (pinfunction "B_2") (pintype "passive"))
    )
    (net (code "61") (name "Net-(T1-C)") (class "Default")
      (node (ref "SV1") (pin "12") (pinfunction "12_12") (pintype "passive"))
      (node (ref "T1") (pin "1") (pinfunction "C_1") (pintype "passive"))
    )
    (net (code "62") (name "Net-(T2-B)") (class "Default")
      (node (ref "R2") (pin "2") (pinfunction "2_2") (pintype "passive"))
      (node (ref "T2") (pin "2") (pinfunction "B_2") (pintype "passive"))
    )
    (net (code "63") (name "Net-(T2-C)") (class "Default")
      (node (ref "SV1") (pin "11") (pinfunction "11_11") (pintype "passive"))
      (node (ref "T2") (pin "1") (pinfunction "C_1") (pintype "passive"))
    )
    (net (code "64") (name "Net-(T3-B)") (class "Default")
      (node (ref "R3") (pin "2") (pinfunction "2_2") (pintype "passive"))
      (node (ref "T3") (pin "2") (pinfunction "B_2") (pintype "passive"))
    )
    (net (code "65") (name "Net-(T3-C)") (class "Default")
      (node (ref "SV1") (pin "10") (pinfunction "10_10") (pintype "passive"))
      (node (ref "T3") (pin "1") (pinfunction "C_1") (pintype "passive"))
    )
    (net (code "66") (name "Net-(T4-B)") (class "Default")
      (node (ref "R4") (pin "2") (pinfunction "2_2") (pintype "passive"))
      (node (ref "T4") (pin "2") (pinfunction "B_2") (pintype "passive"))
    )
    (net (code "67") (name "Net-(T4-C)") (class "Default")
      (node (ref "SV1") (pin "9") (pinfunction "9_9") (pintype "passive"))
      (node (ref "T4") (pin "1") (pinfunction "C_1") (pintype "passive"))
    )
    (net (code "68") (name "Net-(T5-B)") (class "Default")
      (node (ref "R5") (pin "2") (pinfunction "2_2") (pintype "passive"))
      (node (ref "T5") (pin "2") (pinfunction "B_2") (pintype "passive"))
    )
    (net (code "69") (name "Net-(T5-C)") (class "Default")
      (node (ref "SV1") (pin "8") (pinfunction "8_8") (pintype "passive"))
      (node (ref "T5") (pin "1") (pinfunction "C_1") (pintype "passive"))
    )
    (net (code "70") (name "Net-(T6-B)") (class "Default")
      (node (ref "R6") (pin "2") (pinfunction "2_2") (pintype "passive"))
      (node (ref "T6") (pin "2") (pinfunction "B_2") (pintype "passive"))
    )
    (net (code "71") (name "Net-(T6-C)") (class "Default")
      (node (ref "SV1") (pin "7") (pinfunction "7_7") (pintype "passive"))
      (node (ref "T6") (pin "1") (pinfunction "C_1") (pintype "passive"))
    )
    (net (code "72") (name "Net-(T7-B)") (class "Default")
      (node (ref "R7") (pin "2") (pinfunction "2_2") (pintype "passive"))
      (node (ref "T7") (pin "2") (pinfunction "B_2") (pintype "passive"))
    )
    (net (code "73") (name "Net-(T7-C)") (class "Default")
      (node (ref "SV1") (pin "5") (pinfunction "5_5") (pintype "passive"))
      (node (ref "T7") (pin "1") (pinfunction "C_1") (pintype "passive"))
    )
    (net (code "74") (name "Net-(T8-B)") (class "Default")
      (node (ref "R8") (pin "2") (pinfunction "2_2") (pintype "passive"))
      (node (ref "T8") (pin "2") (pinfunction "B_2") (pintype "passive"))
    )
    (net (code "75") (name "Net-(T8-C)") (class "Default")
      (node (ref "SV1") (pin "6") (pinfunction "6_6") (pintype "passive"))
      (node (ref "T8") (pin "1") (pinfunction "C_1") (pintype "passive"))
    )
    (net (code "76") (name "Net-(T9-B)") (class "Default")
      (node (ref "R9") (pin "2") (pinfunction "2_2") (pintype "passive"))
      (node (ref "T9") (pin "2") (pinfunction "B_2") (pintype "passive"))
    )
    (net (code "77") (name "Net-(T9-C)") (class "Default")
      (node (ref "SV1") (pin "3") (pinfunction "3_3") (pintype "passive"))
      (node (ref "T9") (pin "1") (pinfunction "C_1") (pintype "passive"))
    )
    (net (code "78") (name "Net-(T10-B)") (class "Default")
      (node (ref "R10") (pin "2") (pinfunction "2_2") (pintype "passive"))
      (node (ref "T10") (pin "2") (pinfunction "B_2") (pintype "passive"))
    )
    (net (code "79") (name "Net-(T10-C)") (class "Default")
      (node (ref "SV1") (pin "4") (pinfunction "4_4") (pintype "passive"))
      (node (ref "T10") (pin "1") (pinfunction "C_1") (pintype "passive"))
    )
    (net (code "80") (name "Net-(T11-B)") (class "Default")
      (node (ref "R11") (pin "2") (pinfunction "2_2") (pintype "passive"))
      (node (ref "T11") (pin "2") (pinfunction "B_2") (pintype "passive"))
    )
    (net (code "81") (name "Net-(T11-C)") (class "Default")
      (node (ref "SV1") (pin "1") (pinfunction "1_1") (pintype "passive"))
      (node (ref "T11") (pin "1") (pinfunction "C_1") (pintype "passive"))
    )
    (net (code "82") (name "Net-(T12-B)") (class "Default")
      (node (ref "R12") (pin "2") (pinfunction "2_2") (pintype "passive"))
      (node (ref "T12") (pin "2") (pinfunction "B_2") (pintype "passive"))
    )
    (net (code "83") (name "Net-(T12-C)") (class "Default")
      (node (ref "SV1") (pin "2") (pinfunction "2_2") (pintype "passive"))
      (node (ref "T12") (pin "1") (pinfunction "C_1") (pintype "passive"))
    )
    (net (code "84") (name "Net-(T13-B)") (class "Default")
      (node (ref "R14") (pin "2") (pinfunction "2_2") (pintype "passive"))
      (node (ref "T13") (pin "2") (pinfunction "B_2") (pintype "passive"))
    )
    (net (code "85") (name "Net-(T13-C)") (class "Default")
      (node (ref "SV1") (pin "26") (pinfunction "26_26") (pintype "passive"))
      (node (ref "T13") (pin "1") (pinfunction "C_1") (pintype "passive"))
    )
    (net (code "86") (name "Net-(T14-B)") (class "Default")
      (node (ref "R15") (pin "2") (pinfunction "2_2") (pintype "passive"))
      (node (ref "T14") (pin "2") (pinfunction "B_2") (pintype "passive"))
    )
    (net (code "87") (name "Net-(T14-C)") (class "Default")
      (node (ref "SV1") (pin "25") (pinfunction "25_25") (pintype "passive"))
      (node (ref "T14") (pin "1") (pinfunction "C_1") (pintype "passive"))
    )
    (net (code "88") (name "Net-(T15-B)") (class "Default")
      (node (ref "R16") (pin "2") (pinfunction "2_2") (pintype "passive"))
      (node (ref "T15") (pin "2") (pinfunction "B_2") (pintype "passive"))
    )
    (net (code "89") (name "Net-(T15-C)") (class "Default")
      (node (ref "SV1") (pin "24") (pinfunction "24_24") (pintype "passive"))
      (node (ref "T15") (pin "1") (pinfunction "C_1") (pintype "passive"))
    )
    (net (code "90") (name "Net-(T16-B)") (class "Default")
      (node (ref "R17") (pin "2") (pinfunction "2_2") (pintype "passive"))
      (node (ref "T16") (pin "2") (pinfunction "B_2") (pintype "passive"))
    )
    (net (code "91") (name "Net-(T16-C)") (class "Default")
      (node (ref "SV1") (pin "23") (pinfunction "23_23") (pintype "passive"))
      (node (ref "T16") (pin "1") (pinfunction "C_1") (pintype "passive"))
    )
    (net (code "92") (name "Net-(T17-B)") (class "Default")
      (node (ref "R18") (pin "2") (pinfunction "2_2") (pintype "passive"))
      (node (ref "T17") (pin "2") (pinfunction "B_2") (pintype "passive"))
    )
    (net (code "93") (name "Net-(T17-C)") (class "Default")
      (node (ref "SV1") (pin "22") (pinfunction "22_22") (pintype "passive"))
      (node (ref "T17") (pin "1") (pinfunction "C_1") (pintype "passive"))
    )
    (net (code "94") (name "Net-(T18-B)") (class "Default")
      (node (ref "R19") (pin "2") (pinfunction "2_2") (pintype "passive"))
      (node (ref "T18") (pin "2") (pinfunction "B_2") (pintype "passive"))
    )
    (net (code "95") (name "Net-(T18-C)") (class "Default")
      (node (ref "SV1") (pin "21") (pinfunction "21_21") (pintype "passive"))
      (node (ref "T18") (pin "1") (pinfunction "C_1") (pintype "passive"))
    )
    (net (code "96") (name "Net-(T19-B)") (class "Default")
      (node (ref "R20") (pin "2") (pinfunction "2_2") (pintype "passive"))
      (node (ref "T19") (pin "2") (pinfunction "B_2") (pintype "passive"))
    )
    (net (code "97") (name "Net-(T19-C)") (class "Default")
      (node (ref "SV1") (pin "20") (pinfunction "20_20") (pintype "passive"))
      (node (ref "T19") (pin "1") (pinfunction "C_1") (pintype "passive"))
    )
    (net (code "98") (name "Net-(T20-B)") (class "Default")
      (node (ref "R21") (pin "2") (pinfunction "2_2") (pintype "passive"))
      (node (ref "T20") (pin "2") (pinfunction "B_2") (pintype "passive"))
    )
    (net (code "99") (name "Net-(T20-C)") (class "Default")
      (node (ref "SV1") (pin "19") (pinfunction "19_19") (pintype "passive"))
      (node (ref "T20") (pin "1") (pinfunction "C_1") (pintype "passive"))
    )
    (net (code "100") (name "Net-(T21-B)") (class "Default")
      (node (ref "R22") (pin "2") (pinfunction "2_2") (pintype "passive"))
      (node (ref "T21") (pin "2") (pinfunction "B_2") (pintype "passive"))
    )
    (net (code "101") (name "Net-(T21-C)") (class "Default")
      (node (ref "SV1") (pin "17") (pinfunction "17_17") (pintype "passive"))
      (node (ref "T21") (pin "1") (pinfunction "C_1") (pintype "passive"))
    )
    (net (code "102") (name "Net-(T22-B)") (class "Default")
      (node (ref "R23") (pin "2") (pinfunction "2_2") (pintype "passive"))
      (node (ref "T22") (pin "2") (pinfunction "B_2") (pintype "passive"))
    )
    (net (code "103") (name "Net-(T22-C)") (class "Default")
      (node (ref "SV1") (pin "18") (pinfunction "18_18") (pintype "passive"))
      (node (ref "T22") (pin "1") (pinfunction "C_1") (pintype "passive"))
    )
    (net (code "104") (name "Net-(T23-B)") (class "Default")
      (node (ref "R24") (pin "2") (pinfunction "2_2") (pintype "passive"))
      (node (ref "T23") (pin "2") (pinfunction "B_2") (pintype "passive"))
    )
    (net (code "105") (name "Net-(T23-C)") (class "Default")
      (node (ref "SV1") (pin "15") (pinfunction "15_15") (pintype "passive"))
      (node (ref "T23") (pin "1") (pinfunction "C_1") (pintype "passive"))
    )
    (net (code "106") (name "Net-(T24-B)") (class "Default")
      (node (ref "R25") (pin "2") (pinfunction "2_2") (pintype "passive"))
      (node (ref "T24") (pin "2") (pinfunction "B_2") (pintype "passive"))
    )
    (net (code "107") (name "Net-(T24-C)") (class "Default")
      (node (ref "SV1") (pin "16") (pinfunction "16_16") (pintype "passive"))
      (node (ref "T24") (pin "1") (pinfunction "C_1") (pintype "passive"))
    )
    (net (code "108") (name "Net-(T25-B)") (class "Default")
      (node (ref "R27") (pin "2") (pinfunction "2_2") (pintype "passive"))
      (node (ref "T25") (pin "2") (pinfunction "B_2") (pintype "passive"))
    )
    (net (code "109") (name "Net-(T25-C)") (class "Default")
      (node (ref "SV2") (pin "12") (pinfunction "12_12") (pintype "passive"))
      (node (ref "T25") (pin "1") (pinfunction "C_1") (pintype "passive"))
    )
    (net (code "110") (name "Net-(T26-B)") (class "Default")
      (node (ref "R28") (pin "2") (pinfunction "2_2") (pintype "passive"))
      (node (ref "T26") (pin "2") (pinfunction "B_2") (pintype "passive"))
    )
    (net (code "111") (name "Net-(T26-C)") (class "Default")
      (node (ref "SV2") (pin "11") (pinfunction "11_11") (pintype "passive"))
      (node (ref "T26") (pin "1") (pinfunction "C_1") (pintype "passive"))
    )
    (net (code "112") (name "Net-(T27-B)") (class "Default")
      (node (ref "R29") (pin "2") (pinfunction "2_2") (pintype "passive"))
      (node (ref "T27") (pin "2") (pinfunction "B_2") (pintype "passive"))
    )
    (net (code "113") (name "Net-(T27-C)") (class "Default")
      (node (ref "SV2") (pin "10") (pinfunction "10_10") (pintype "passive"))
      (node (ref "T27") (pin "1") (pinfunction "C_1") (pintype "passive"))
    )
    (net (code "114") (name "Net-(T28-B)") (class "Default")
      (node (ref "R30") (pin "2") (pinfunction "2_2") (pintype "passive"))
      (node (ref "T28") (pin "2") (pinfunction "B_2") (pintype "passive"))
    )
    (net (code "115") (name "Net-(T28-C)") (class "Default")
      (node (ref "SV2") (pin "9") (pinfunction "9_9") (pintype "passive"))
      (node (ref "T28") (pin "1") (pinfunction "C_1") (pintype "passive"))
    )
    (net (code "116") (name "Net-(T29-B)") (class "Default")
      (node (ref "R31") (pin "2") (pinfunction "2_2") (pintype "passive"))
      (node (ref "T29") (pin "2") (pinfunction "B_2") (pintype "passive"))
    )
    (net (code "117") (name "Net-(T29-C)") (class "Default")
      (node (ref "SV2") (pin "8") (pinfunction "8_8") (pintype "passive"))
      (node (ref "T29") (pin "1") (pinfunction "C_1") (pintype "passive"))
    )
    (net (code "118") (name "Net-(T30-B)") (class "Default")
      (node (ref "R32") (pin "2") (pinfunction "2_2") (pintype "passive"))
      (node (ref "T30") (pin "2") (pinfunction "B_2") (pintype "passive"))
    )
    (net (code "119") (name "Net-(T30-C)") (class "Default")
      (node (ref "SV2") (pin "7") (pinfunction "7_7") (pintype "passive"))
      (node (ref "T30") (pin "1") (pinfunction "C_1") (pintype "passive"))
    )
    (net (code "120") (name "Net-(T31-B)") (class "Default")
      (node (ref "R33") (pin "2") (pinfunction "2_2") (pintype "passive"))
      (node (ref "T31") (pin "2") (pinfunction "B_2") (pintype "passive"))
    )
    (net (code "121") (name "Net-(T31-C)") (class "Default")
      (node (ref "SV2") (pin "5") (pinfunction "5_5") (pintype "passive"))
      (node (ref "T31") (pin "1") (pinfunction "C_1") (pintype "passive"))
    )
    (net (code "122") (name "Net-(T32-B)") (class "Default")
      (node (ref "R34") (pin "2") (pinfunction "2_2") (pintype "passive"))
      (node (ref "T32") (pin "2") (pinfunction "B_2") (pintype "passive"))
    )
    (net (code "123") (name "Net-(T32-C)") (class "Default")
      (node (ref "SV2") (pin "6") (pinfunction "6_6") (pintype "passive"))
      (node (ref "T32") (pin "1") (pinfunction "C_1") (pintype "passive"))
    )
    (net (code "124") (name "Net-(T33-B)") (class "Default")
      (node (ref "R35") (pin "2") (pinfunction "2_2") (pintype "passive"))
      (node (ref "T33") (pin "2") (pinfunction "B_2") (pintype "passive"))
    )
    (net (code "125") (name "Net-(T33-C)") (class "Default")
      (node (ref "SV2") (pin "3") (pinfunction "3_3") (pintype "passive"))
      (node (ref "T33") (pin "1") (pinfunction "C_1") (pintype "passive"))
    )
    (net (code "126") (name "Net-(T34-B)") (class "Default")
      (node (ref "R36") (pin "2") (pinfunction "2_2") (pintype "passive"))
      (node (ref "T34") (pin "2") (pinfunction "B_2") (pintype "passive"))
    )
    (net (code "127") (name "Net-(T34-C)") (class "Default")
      (node (ref "SV2") (pin "4") (pinfunction "4_4") (pintype "passive"))
      (node (ref "T34") (pin "1") (pinfunction "C_1") (pintype "passive"))
    )
    (net (code "128") (name "Net-(T35-B)") (class "Default")
      (node (ref "R37") (pin "2") (pinfunction "2_2") (pintype "passive"))
      (node (ref "T35") (pin "2") (pinfunction "B_2") (pintype "passive"))
    )
    (net (code "129") (name "Net-(T35-C)") (class "Default")
      (node (ref "SV2") (pin "1") (pinfunction "1_1") (pintype "passive"))
      (node (ref "T35") (pin "1") (pinfunction "C_1") (pintype "passive"))
    )
    (net (code "130") (name "Net-(T36-B)") (class "Default")
      (node (ref "R38") (pin "2") (pinfunction "2_2") (pintype "passive"))
      (node (ref "T36") (pin "2") (pinfunction "B_2") (pintype "passive"))
    )
    (net (code "131") (name "Net-(T36-C)") (class "Default")
      (node (ref "SV2") (pin "2") (pinfunction "2_2") (pintype "passive"))
      (node (ref "T36") (pin "1") (pinfunction "C_1") (pintype "passive"))
    )
    (net (code "132") (name "Net-(T37-B)") (class "Default")
      (node (ref "R40") (pin "2") (pinfunction "2_2") (pintype "passive"))
      (node (ref "T37") (pin "2") (pinfunction "B_2") (pintype "passive"))
    )
    (net (code "133") (name "Net-(T37-C)") (class "Default")
      (node (ref "SV2") (pin "26") (pinfunction "26_26") (pintype "passive"))
      (node (ref "T37") (pin "1") (pinfunction "C_1") (pintype "passive"))
    )
    (net (code "134") (name "Net-(T38-B)") (class "Default")
      (node (ref "R41") (pin "2") (pinfunction "2_2") (pintype "passive"))
      (node (ref "T38") (pin "2") (pinfunction "B_2") (pintype "passive"))
    )
    (net (code "135") (name "Net-(T38-C)") (class "Default")
      (node (ref "SV2") (pin "25") (pinfunction "25_25") (pintype "passive"))
      (node (ref "T38") (pin "1") (pinfunction "C_1") (pintype "passive"))
    )
    (net (code "136") (name "Net-(T39-B)") (class "Default")
      (node (ref "R42") (pin "2") (pinfunction "2_2") (pintype "passive"))
      (node (ref "T39") (pin "2") (pinfunction "B_2") (pintype "passive"))
    )
    (net (code "137") (name "Net-(T39-C)") (class "Default")
      (node (ref "SV2") (pin "24") (pinfunction "24_24") (pintype "passive"))
      (node (ref "T39") (pin "1") (pinfunction "C_1") (pintype "passive"))
    )
    (net (code "138") (name "Net-(T40-B)") (class "Default")
      (node (ref "R43") (pin "2") (pinfunction "2_2") (pintype "passive"))
      (node (ref "T40") (pin "2") (pinfunction "B_2") (pintype "passive"))
    )
    (net (code "139") (name "Net-(T40-C)") (class "Default")
      (node (ref "SV2") (pin "23") (pinfunction "23_23") (pintype "passive"))
      (node (ref "T40") (pin "1") (pinfunction "C_1") (pintype "passive"))
    )
    (net (code "140") (name "Net-(T41-B)") (class "Default")
      (node (ref "R44") (pin "2") (pinfunction "2_2") (pintype "passive"))
      (node (ref "T41") (pin "2") (pinfunction "B_2") (pintype "passive"))
    )
    (net (code "141") (name "Net-(T41-C)") (class "Default")
      (node (ref "SV2") (pin "22") (pinfunction "22_22") (pintype "passive"))
      (node (ref "T41") (pin "1") (pinfunction "C_1") (pintype "passive"))
    )
    (net (code "142") (name "Net-(T42-B)") (class "Default")
      (node (ref "R45") (pin "2") (pinfunction "2_2") (pintype "passive"))
      (node (ref "T42") (pin "2") (pinfunction "B_2") (pintype "passive"))
    )
    (net (code "143") (name "Net-(T42-C)") (class "Default")
      (node (ref "SV2") (pin "21") (pinfunction "21_21") (pintype "passive"))
      (node (ref "T42") (pin "1") (pinfunction "C_1") (pintype "passive"))
    )
    (net (code "144") (name "Net-(T43-B)") (class "Default")
      (node (ref "R46") (pin "2") (pinfunction "2_2") (pintype "passive"))
      (node (ref "T43") (pin "2") (pinfunction "B_2") (pintype "passive"))
    )
    (net (code "145") (name "Net-(T43-C)") (class "Default")
      (node (ref "SV2") (pin "20") (pinfunction "20_20") (pintype "passive"))
      (node (ref "T43") (pin "1") (pinfunction "C_1") (pintype "passive"))
    )
    (net (code "146") (name "Net-(T44-B)") (class "Default")
      (node (ref "R47") (pin "2") (pinfunction "2_2") (pintype "passive"))
      (node (ref "T44") (pin "2") (pinfunction "B_2") (pintype "passive"))
    )
    (net (code "147") (name "Net-(T44-C)") (class "Default")
      (node (ref "SV2") (pin "19") (pinfunction "19_19") (pintype "passive"))
      (node (ref "T44") (pin "1") (pinfunction "C_1") (pintype "passive"))
    )
    (net (code "148") (name "Net-(T45-B)") (class "Default")
      (node (ref "R48") (pin "2") (pinfunction "2_2") (pintype "passive"))
      (node (ref "T45") (pin "2") (pinfunction "B_2") (pintype "passive"))
    )
    (net (code "149") (name "Net-(T45-C)") (class "Default")
      (node (ref "SV2") (pin "17") (pinfunction "17_17") (pintype "passive"))
      (node (ref "T45") (pin "1") (pinfunction "C_1") (pintype "passive"))
    )
    (net (code "150") (name "Net-(T46-B)") (class "Default")
      (node (ref "R49") (pin "2") (pinfunction "2_2") (pintype "passive"))
      (node (ref "T46") (pin "2") (pinfunction "B_2") (pintype "passive"))
    )
    (net (code "151") (name "Net-(T46-C)") (class "Default")
      (node (ref "SV2") (pin "18") (pinfunction "18_18") (pintype "passive"))
      (node (ref "T46") (pin "1") (pinfunction "C_1") (pintype "passive"))
    )
    (net (code "152") (name "Net-(T47-B)") (class "Default")
      (node (ref "R50") (pin "2") (pinfunction "2_2") (pintype "passive"))
      (node (ref "T47") (pin "2") (pinfunction "B_2") (pintype "passive"))
    )
    (net (code "153") (name "Net-(T47-C)") (class "Default")
      (node (ref "SV2") (pin "15") (pinfunction "15_15") (pintype "passive"))
      (node (ref "T47") (pin "1") (pinfunction "C_1") (pintype "passive"))
    )
    (net (code "154") (name "Net-(T48-B)") (class "Default")
      (node (ref "R51") (pin "2") (pinfunction "2_2") (pintype "passive"))
      (node (ref "T48") (pin "2") (pinfunction "B_2") (pintype "passive"))
    )
    (net (code "155") (name "Net-(T48-C)") (class "Default")
      (node (ref "SV2") (pin "16") (pinfunction "16_16") (pintype "passive"))
      (node (ref "T48") (pin "1") (pinfunction "C_1") (pintype "passive"))
    )
    (net (code "156") (name "VCC") (class "Default")
      (node (ref "IC1") (pin "10") (pinfunction "SCL_10") (pintype "input"))
      (node (ref "IC2") (pin "10") (pinfunction "SCL_10") (pintype "input"))
      (node (ref "IC3") (pin "10") (pinfunction "SCL_10") (pintype "input"))
      (node (ref "IC4") (pin "10") (pinfunction "SCL_10") (pintype "input"))
      (node (ref "IC5") (pin "10") (pinfunction "SCL_10") (pintype "input"))
      (node (ref "IC6") (pin "10") (pinfunction "SCL_10") (pintype "input"))
    )
    (net (code "157") (name "unconnected-(R13-Pad1)") (class "Default")
      (node (ref "R13") (pin "1") (pinfunction "1_1") (pintype "passive"))
    )
    (net (code "158") (name "unconnected-(R26-Pad1)") (class "Default")
      (node (ref "R26") (pin "1") (pinfunction "1_1") (pintype "passive"))
    )
    (net (code "159") (name "unconnected-(R39-Pad1)") (class "Default")
      (node (ref "R39") (pin "1") (pinfunction "1_1") (pintype "passive"))
    )
    (net (code "160") (name "unconnected-(R52-Pad1)") (class "Default")
      (node (ref "R52") (pin "1") (pinfunction "1_1") (pintype "passive"))
    )
    (net (code "161") (name "unconnected-(SV1-Pad13)") (class "Default")
      (node (ref "SV1") (pin "13") (pinfunction "13_13") (pintype "passive"))
    )
    (net (code "162") (name "unconnected-(SV1-Pad14)") (class "Default")
      (node (ref "SV1") (pin "14") (pinfunction "14_14") (pintype "passive"))
    )
    (net (code "163") (name "unconnected-(SV2-Pad13)") (class "Default")
      (node (ref "SV2") (pin "13") (pinfunction "13_13") (pintype "passive"))
    )
    (net (code "164") (name "unconnected-(SV2-Pad14)") (class "Default")
      (node (ref "SV2") (pin "14") (pinfunction "14_14") (pintype "passive"))
    )
  )
)
